# atWork_Encoder.net
KiCad netlist of a schematic drawn in Altium Designer
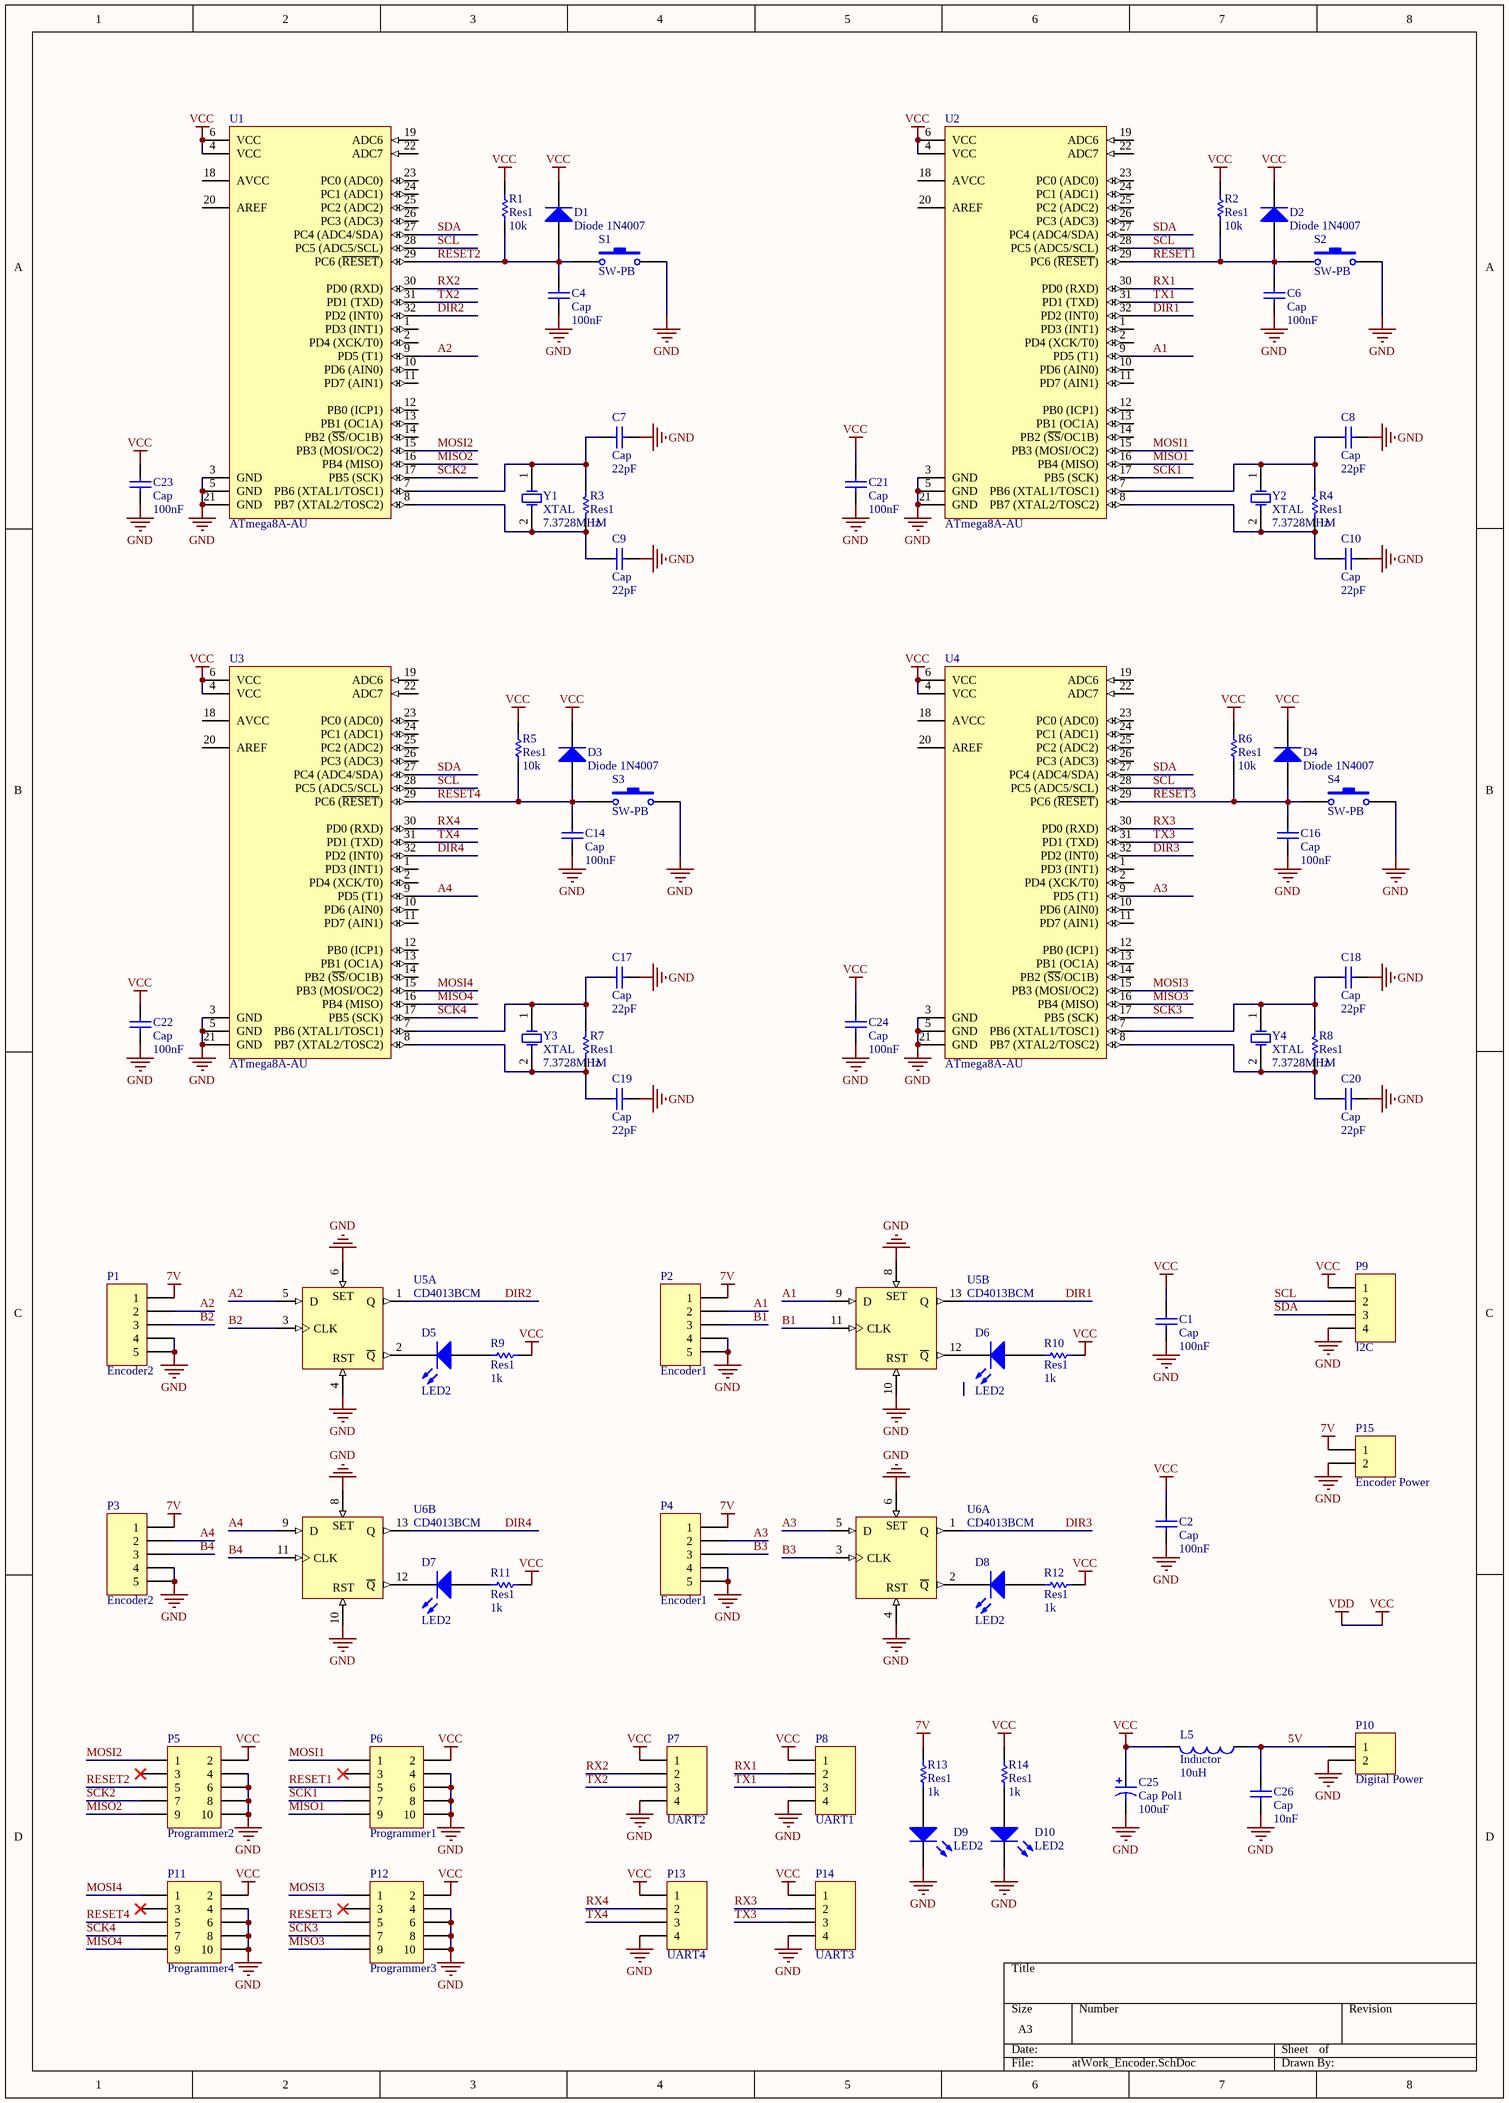
[diagram p0: atWork_Encoder.SchDoc]

(export (version "E")
  (design (tool "Eeschema 10.0.6"))
  (components
    (comp (ref "C1")
      (value "Cap")
      (footprint "C1206")
      (description "Capacitor")
      (fields (field (name "ALTIUM_VALUE") "100nF") (field (name "PUBLISHER") "Altium Limited"))
      (libsource (lib "Miscellaneous Devices") (part "Cap"))
    )
    (comp (ref "C2")
      (value "Cap")
      (footprint "C1206")
      (description "Capacitor")
      (fields (field (name "ALTIUM_VALUE") "100nF") (field (name "PUBLISHER") "Altium Limited"))
      (libsource (lib "Miscellaneous Devices") (part "Cap"))
    )
    (comp (ref "C4")
      (value "Cap")
      (footprint "C1206")
      (description "Capacitor")
      (fields (field (name "ALTIUM_VALUE") "100nF") (field (name "PUBLISHER") "Altium Limited"))
      (libsource (lib "Miscellaneous Devices") (part "Cap"))
    )
    (comp (ref "C6")
      (value "Cap")
      (footprint "C1206")
      (description "Capacitor")
      (fields (field (name "ALTIUM_VALUE") "100nF") (field (name "PUBLISHER") "Altium Limited"))
      (libsource (lib "Miscellaneous Devices") (part "Cap"))
    )
    (comp (ref "C7")
      (value "Cap")
      (footprint "C1206")
      (description "Capacitor")
      (fields (field (name "ALTIUM_VALUE") "22pF") (field (name "PUBLISHER") "Altium Limited"))
      (libsource (lib "Miscellaneous Devices") (part "Cap"))
    )
    (comp (ref "C8")
      (value "Cap")
      (footprint "C1206")
      (description "Capacitor")
      (fields (field (name "ALTIUM_VALUE") "22pF") (field (name "PUBLISHER") "Altium Limited"))
      (libsource (lib "Miscellaneous Devices") (part "Cap"))
    )
    (comp (ref "C9")
      (value "Cap")
      (footprint "C1206")
      (description "Capacitor")
      (fields (field (name "ALTIUM_VALUE") "22pF") (field (name "PUBLISHER") "Altium Limited"))
      (libsource (lib "Miscellaneous Devices") (part "Cap"))
    )
    (comp (ref "C10")
      (value "Cap")
      (footprint "C1206")
      (description "Capacitor")
      (fields (field (name "ALTIUM_VALUE") "22pF") (field (name "PUBLISHER") "Altium Limited"))
      (libsource (lib "Miscellaneous Devices") (part "Cap"))
    )
    (comp (ref "C14")
      (value "Cap")
      (footprint "C1206")
      (description "Capacitor")
      (fields (field (name "ALTIUM_VALUE") "100nF") (field (name "PUBLISHER") "Altium Limited"))
      (libsource (lib "Miscellaneous Devices") (part "Cap"))
    )
    (comp (ref "C16")
      (value "Cap")
      (footprint "C1206")
      (description "Capacitor")
      (fields (field (name "ALTIUM_VALUE") "100nF") (field (name "PUBLISHER") "Altium Limited"))
      (libsource (lib "Miscellaneous Devices") (part "Cap"))
    )
    (comp (ref "C17")
      (value "Cap")
      (footprint "C1206")
      (description "Capacitor")
      (fields (field (name "ALTIUM_VALUE") "22pF") (field (name "PUBLISHER") "Altium Limited"))
      (libsource (lib "Miscellaneous Devices") (part "Cap"))
    )
    (comp (ref "C18")
      (value "Cap")
      (footprint "C1206")
      (description "Capacitor")
      (fields (field (name "ALTIUM_VALUE") "22pF") (field (name "PUBLISHER") "Altium Limited"))
      (libsource (lib "Miscellaneous Devices") (part "Cap"))
    )
    (comp (ref "C19")
      (value "Cap")
      (footprint "C1206")
      (description "Capacitor")
      (fields (field (name "ALTIUM_VALUE") "22pF") (field (name "PUBLISHER") "Altium Limited"))
      (libsource (lib "Miscellaneous Devices") (part "Cap"))
    )
    (comp (ref "C20")
      (value "Cap")
      (footprint "C1206")
      (description "Capacitor")
      (fields (field (name "ALTIUM_VALUE") "22pF") (field (name "PUBLISHER") "Altium Limited"))
      (libsource (lib "Miscellaneous Devices") (part "Cap"))
    )
    (comp (ref "C21")
      (value "Cap")
      (footprint "C1206")
      (description "Capacitor")
      (fields (field (name "ALTIUM_VALUE") "100nF") (field (name "PUBLISHER") "Altium Limited"))
      (libsource (lib "Miscellaneous Devices") (part "Cap"))
    )
    (comp (ref "C22")
      (value "Cap")
      (footprint "C1206")
      (description "Capacitor")
      (fields (field (name "ALTIUM_VALUE") "100nF") (field (name "PUBLISHER") "Altium Limited"))
      (libsource (lib "Miscellaneous Devices") (part "Cap"))
    )
    (comp (ref "C23")
      (value "Cap")
      (footprint "C1206")
      (description "Capacitor")
      (fields (field (name "ALTIUM_VALUE") "100nF") (field (name "PUBLISHER") "Altium Limited"))
      (libsource (lib "Miscellaneous Devices") (part "Cap"))
    )
    (comp (ref "C24")
      (value "Cap")
      (footprint "C1206")
      (description "Capacitor")
      (fields (field (name "ALTIUM_VALUE") "100nF") (field (name "PUBLISHER") "Altium Limited"))
      (libsource (lib "Miscellaneous Devices") (part "Cap"))
    )
    (comp (ref "C25")
      (value "Cap Pol1")
      (footprint "CAP-SMD1")
      (description "Polarized Capacitor (Radial)")
      (fields (field (name "ALTIUM_VALUE") "100uF") (field (name "PUBLISHER") "Altium Limited"))
      (libsource (lib "Miscellaneous Devices") (part "Cap Pol1"))
    )
    (comp (ref "C26")
      (value "Cap")
      (footprint "C1206")
      (description "Capacitor")
      (fields (field (name "ALTIUM_VALUE") "10nF") (field (name "PUBLISHER") "Altium Limited"))
      (libsource (lib "Miscellaneous Devices") (part "Cap"))
    )
    (comp (ref "D1")
      (value "Diode 1N4007")
      (footprint "DIODE-SMD")
      (description "1 Amp General Purpose Rectifier")
      (fields (field (name "PUBLISHER") "Altium Limited"))
      (libsource (lib "Miscellaneous Devices") (part "Diode 1N4007"))
    )
    (comp (ref "D2")
      (value "Diode 1N4007")
      (footprint "DIODE-SMD")
      (description "1 Amp General Purpose Rectifier")
      (fields (field (name "PUBLISHER") "Altium Limited"))
      (libsource (lib "Miscellaneous Devices") (part "Diode 1N4007"))
    )
    (comp (ref "D3")
      (value "Diode 1N4007")
      (footprint "DIODE-SMD")
      (description "1 Amp General Purpose Rectifier")
      (fields (field (name "PUBLISHER") "Altium Limited"))
      (libsource (lib "Miscellaneous Devices") (part "Diode 1N4007"))
    )
    (comp (ref "D4")
      (value "Diode 1N4007")
      (footprint "DIODE-SMD")
      (description "1 Amp General Purpose Rectifier")
      (fields (field (name "PUBLISHER") "Altium Limited"))
      (libsource (lib "Miscellaneous Devices") (part "Diode 1N4007"))
    )
    (comp (ref "D5")
      (value "LED2")
      (footprint "3.2X1.6X1.1")
      (description "Typical RED, GREEN, YELLOW, AMBER GaAs LED")
      (fields (field (name "PUBLISHER") "Altium Limited"))
      (libsource (lib "Miscellaneous Devices") (part "LED2"))
    )
    (comp (ref "D6")
      (value "LED2")
      (footprint "3.2X1.6X1.1")
      (description "Typical RED, GREEN, YELLOW, AMBER GaAs LED")
      (fields (field (name "PUBLISHER") "Altium Limited"))
      (libsource (lib "Miscellaneous Devices") (part "LED2"))
    )
    (comp (ref "D7")
      (value "LED2")
      (footprint "3.2X1.6X1.1")
      (description "Typical RED, GREEN, YELLOW, AMBER GaAs LED")
      (fields (field (name "PUBLISHER") "Altium Limited"))
      (libsource (lib "Miscellaneous Devices") (part "LED2"))
    )
    (comp (ref "D8")
      (value "LED2")
      (footprint "3.2X1.6X1.1")
      (description "Typical RED, GREEN, YELLOW, AMBER GaAs LED")
      (fields (field (name "PUBLISHER") "Altium Limited"))
      (libsource (lib "Miscellaneous Devices") (part "LED2"))
    )
    (comp (ref "D9")
      (value "LED2")
      (footprint "3.2X1.6X1.1")
      (description "Typical RED, GREEN, YELLOW, AMBER GaAs LED")
      (fields (field (name "PUBLISHER") "Altium Limited"))
      (libsource (lib "Miscellaneous Devices") (part "LED2"))
    )
    (comp (ref "D10")
      (value "LED2")
      (footprint "3.2X1.6X1.1")
      (description "Typical RED, GREEN, YELLOW, AMBER GaAs LED")
      (fields (field (name "PUBLISHER") "Altium Limited"))
      (libsource (lib "Miscellaneous Devices") (part "LED2"))
    )
    (comp (ref "L5")
      (value "Inductor")
      (footprint "C1206")
      (fields (field (name "ALTIUM_VALUE") "10uH") (field (name "PUBLISHER") "Altium Limited"))
      (libsource (lib "Miscellaneous Devices") (part "Inductor"))
    )
    (comp (ref "P1")
      (value "Encoder2")
      (footprint "XH5PIN")
      (description "Header, 5-Pin")
      (fields (field (name "PUBLISHER") "Altium Limited"))
      (libsource (lib "Miscellaneous Connectors") (part "Header 5"))
    )
    (comp (ref "P2")
      (value "Encoder1")
      (footprint "XH5PIN")
      (description "Header, 5-Pin")
      (fields (field (name "PUBLISHER") "Altium Limited"))
      (libsource (lib "Miscellaneous Connectors") (part "Header 5"))
    )
    (comp (ref "P3")
      (value "Encoder2")
      (footprint "XH5PIN")
      (description "Header, 5-Pin")
      (fields (field (name "PUBLISHER") "Altium Limited"))
      (libsource (lib "Miscellaneous Connectors") (part "Header 5"))
    )
    (comp (ref "P4")
      (value "Encoder1")
      (footprint "XH5PIN")
      (description "Header, 5-Pin")
      (fields (field (name "PUBLISHER") "Altium Limited"))
      (libsource (lib "Miscellaneous Connectors") (part "Header 5"))
    )
    (comp (ref "P5")
      (value "Programmer2")
      (footprint "BOX2X5")
      (description "Box, 5-Pin, Dual row")
      (fields (field (name "DESIGNER") "Meysam Parvizi") (field (name "EMAIL") "meysam.parvizi.ir@gmail.com"))
      (libsource (lib "mp") (part "Box 5X2"))
    )
    (comp (ref "P6")
      (value "Programmer1")
      (footprint "BOX2X5")
      (description "Box, 5-Pin, Dual row")
      (fields (field (name "DESIGNER") "Meysam Parvizi") (field (name "EMAIL") "meysam.parvizi.ir@gmail.com"))
      (libsource (lib "mp") (part "Box 5X2"))
    )
    (comp (ref "P7")
      (value "UART2")
      (footprint "XH4PIN")
      (description "Header, 4-Pin")
      (fields (field (name "PUBLISHER") "Altium Limited"))
      (libsource (lib "Miscellaneous Connectors") (part "Header 4"))
    )
    (comp (ref "P8")
      (value "UART1")
      (footprint "XH4PIN")
      (description "Header, 4-Pin")
      (fields (field (name "PUBLISHER") "Altium Limited"))
      (libsource (lib "Miscellaneous Connectors") (part "Header 4"))
    )
    (comp (ref "P9")
      (value "I2C")
      (footprint "XH4PIN")
      (description "Header, 4-Pin")
      (fields (field (name "PUBLISHER") "Altium Limited"))
      (libsource (lib "Miscellaneous Connectors") (part "Header 4"))
    )
    (comp (ref "P10")
      (value "Digital Power")
      (footprint "XH2PIN")
      (description "Header, 2-Pin")
      (fields (field (name "PUBLISHER") "Altium Limited"))
      (libsource (lib "Miscellaneous Connectors") (part "Header 2"))
    )
    (comp (ref "P11")
      (value "Programmer4")
      (footprint "BOX2X5")
      (description "Box, 5-Pin, Dual row")
      (fields (field (name "DESIGNER") "Meysam Parvizi") (field (name "EMAIL") "meysam.parvizi.ir@gmail.com"))
      (libsource (lib "mp") (part "Box 5X2"))
    )
    (comp (ref "P12")
      (value "Programmer3")
      (footprint "BOX2X5")
      (description "Box, 5-Pin, Dual row")
      (fields (field (name "DESIGNER") "Meysam Parvizi") (field (name "EMAIL") "meysam.parvizi.ir@gmail.com"))
      (libsource (lib "mp") (part "Box 5X2"))
    )
    (comp (ref "P13")
      (value "UART4")
      (footprint "XH4PIN")
      (description "Header, 4-Pin")
      (fields (field (name "PUBLISHER") "Altium Limited"))
      (libsource (lib "Miscellaneous Connectors") (part "Header 4"))
    )
    (comp (ref "P14")
      (value "UART3")
      (footprint "XH4PIN")
      (description "Header, 4-Pin")
      (fields (field (name "PUBLISHER") "Altium Limited"))
      (libsource (lib "Miscellaneous Connectors") (part "Header 4"))
    )
    (comp (ref "P15")
      (value "Encoder Power")
      (footprint "XH2PIN")
      (description "Header, 2-Pin")
      (fields (field (name "PUBLISHER") "Altium Limited"))
      (libsource (lib "Miscellaneous Connectors") (part "Header 2"))
    )
    (comp (ref "R1")
      (value "Res1")
      (footprint "C1206")
      (description "Resistor")
      (fields (field (name "ALTIUM_VALUE") "10k") (field (name "PUBLISHER") "Altium Limited"))
      (libsource (lib "Miscellaneous Devices") (part "Res1"))
    )
    (comp (ref "R2")
      (value "Res1")
      (footprint "C1206")
      (description "Resistor")
      (fields (field (name "ALTIUM_VALUE") "10k") (field (name "PUBLISHER") "Altium Limited"))
      (libsource (lib "Miscellaneous Devices") (part "Res1"))
    )
    (comp (ref "R3")
      (value "Res1")
      (footprint "C1206")
      (description "Resistor")
      (fields (field (name "ALTIUM_VALUE") "1M") (field (name "PUBLISHER") "Altium Limited"))
      (libsource (lib "Miscellaneous Devices") (part "Res1"))
    )
    (comp (ref "R4")
      (value "Res1")
      (footprint "C1206")
      (description "Resistor")
      (fields (field (name "ALTIUM_VALUE") "1M") (field (name "PUBLISHER") "Altium Limited"))
      (libsource (lib "Miscellaneous Devices") (part "Res1"))
    )
    (comp (ref "R5")
      (value "Res1")
      (footprint "C1206")
      (description "Resistor")
      (fields (field (name "ALTIUM_VALUE") "10k") (field (name "PUBLISHER") "Altium Limited"))
      (libsource (lib "Miscellaneous Devices") (part "Res1"))
    )
    (comp (ref "R6")
      (value "Res1")
      (footprint "C1206")
      (description "Resistor")
      (fields (field (name "ALTIUM_VALUE") "10k") (field (name "PUBLISHER") "Altium Limited"))
      (libsource (lib "Miscellaneous Devices") (part "Res1"))
    )
    (comp (ref "R7")
      (value "Res1")
      (footprint "C1206")
      (description "Resistor")
      (fields (field (name "ALTIUM_VALUE") "1M") (field (name "PUBLISHER") "Altium Limited"))
      (libsource (lib "Miscellaneous Devices") (part "Res1"))
    )
    (comp (ref "R8")
      (value "Res1")
      (footprint "C1206")
      (description "Resistor")
      (fields (field (name "ALTIUM_VALUE") "1M") (field (name "PUBLISHER") "Altium Limited"))
      (libsource (lib "Miscellaneous Devices") (part "Res1"))
    )
    (comp (ref "R9")
      (value "Res1")
      (footprint "C1206")
      (description "Resistor")
      (fields (field (name "ALTIUM_VALUE") "1k") (field (name "PUBLISHER") "Altium Limited"))
      (libsource (lib "Miscellaneous Devices") (part "Res1"))
    )
    (comp (ref "R10")
      (value "Res1")
      (footprint "C1206")
      (description "Resistor")
      (fields (field (name "ALTIUM_VALUE") "1k") (field (name "PUBLISHER") "Altium Limited"))
      (libsource (lib "Miscellaneous Devices") (part "Res1"))
    )
    (comp (ref "R11")
      (value "Res1")
      (footprint "C1206")
      (description "Resistor")
      (fields (field (name "ALTIUM_VALUE") "1k") (field (name "PUBLISHER") "Altium Limited"))
      (libsource (lib "Miscellaneous Devices") (part "Res1"))
    )
    (comp (ref "R12")
      (value "Res1")
      (footprint "C1206")
      (description "Resistor")
      (fields (field (name "ALTIUM_VALUE") "1k") (field (name "PUBLISHER") "Altium Limited"))
      (libsource (lib "Miscellaneous Devices") (part "Res1"))
    )
    (comp (ref "R13")
      (value "Res1")
      (footprint "C1206")
      (description "Resistor")
      (fields (field (name "ALTIUM_VALUE") "1k") (field (name "PUBLISHER") "Altium Limited"))
      (libsource (lib "Miscellaneous Devices") (part "Res1"))
    )
    (comp (ref "R14")
      (value "Res1")
      (footprint "C1206")
      (description "Resistor")
      (fields (field (name "ALTIUM_VALUE") "1k") (field (name "PUBLISHER") "Altium Limited"))
      (libsource (lib "Miscellaneous Devices") (part "Res1"))
    )
    (comp (ref "S1")
      (value "SW-PB")
      (footprint "PUSH1")
      (description "Switch")
      (fields (field (name "PUBLISHER") "Altium Limited"))
      (libsource (lib "Miscellaneous Devices") (part "SW-PB"))
    )
    (comp (ref "S2")
      (value "SW-PB")
      (footprint "PUSH1")
      (description "Switch")
      (fields (field (name "PUBLISHER") "Altium Limited"))
      (libsource (lib "Miscellaneous Devices") (part "SW-PB"))
    )
    (comp (ref "S3")
      (value "SW-PB")
      (footprint "PUSH1")
      (description "Switch")
      (fields (field (name "PUBLISHER") "Altium Limited"))
      (libsource (lib "Miscellaneous Devices") (part "SW-PB"))
    )
    (comp (ref "S4")
      (value "SW-PB")
      (footprint "PUSH1")
      (description "Switch")
      (fields (field (name "PUBLISHER") "Altium Limited"))
      (libsource (lib "Miscellaneous Devices") (part "SW-PB"))
    )
    (comp (ref "U1")
      (value "ATmega8A-AU")
      (footprint "32A_M")
      (fields (field (name "PUBLISHER") "Altium Limited"))
      (libsource (lib "Atmel Microcontroller 8-Bit megaAVR") (part "ATmega8A-AU"))
    )
    (comp (ref "U2")
      (value "ATmega8A-AU")
      (footprint "32A_M")
      (fields (field (name "PUBLISHER") "Altium Limited"))
      (libsource (lib "Atmel Microcontroller 8-Bit megaAVR") (part "ATmega8A-AU"))
    )
    (comp (ref "U3")
      (value "ATmega8A-AU")
      (footprint "32A_M")
      (fields (field (name "PUBLISHER") "Altium Limited"))
      (libsource (lib "Atmel Microcontroller 8-Bit megaAVR") (part "ATmega8A-AU"))
    )
    (comp (ref "U4")
      (value "ATmega8A-AU")
      (footprint "32A_M")
      (fields (field (name "PUBLISHER") "Altium Limited"))
      (libsource (lib "Atmel Microcontroller 8-Bit megaAVR") (part "ATmega8A-AU"))
    )
    (comp (ref "U5")
      (value "CD4013BCM")
      (footprint "M14A_M")
      (description "Dual D-Type Flip-Flop")
      (fields (field (name "PUBLISHER") "Altium Limited"))
      (libsource (lib "FSC Logic Flip-Flop") (part "CD4013BCM"))
    )
    (comp (ref "U6")
      (value "CD4013BCM")
      (footprint "M14A_M")
      (description "Dual D-Type Flip-Flop")
      (fields (field (name "PUBLISHER") "Altium Limited"))
      (libsource (lib "FSC Logic Flip-Flop") (part "CD4013BCM"))
    )
    (comp (ref "Y1")
      (value "XTAL")
      (footprint "XTAL")
      (description "Crystal Oscillator")
      (fields
        (field (name "ALTIUM_VALUE") "7.3728MHz")
        (field (name "DESIGNER") "Meysam Parvizi")
        (field (name "EMAIL") "meysam.parvizi.ir@gmail.com")
      )
      (libsource (lib "mp") (part "XTAL"))
    )
    (comp (ref "Y2")
      (value "XTAL")
      (footprint "XTAL")
      (description "Crystal Oscillator")
      (fields
        (field (name "ALTIUM_VALUE") "7.3728MHz")
        (field (name "DESIGNER") "Meysam Parvizi")
        (field (name "EMAIL") "meysam.parvizi.ir@gmail.com")
      )
      (libsource (lib "mp") (part "XTAL"))
    )
    (comp (ref "Y3")
      (value "XTAL")
      (footprint "XTAL")
      (description "Crystal Oscillator")
      (fields
        (field (name "ALTIUM_VALUE") "7.3728MHz")
        (field (name "DESIGNER") "Meysam Parvizi")
        (field (name "EMAIL") "meysam.parvizi.ir@gmail.com")
      )
      (libsource (lib "mp") (part "XTAL"))
    )
    (comp (ref "Y4")
      (value "XTAL")
      (footprint "XTAL")
      (description "Crystal Oscillator")
      (fields
        (field (name "ALTIUM_VALUE") "7.3728MHz")
        (field (name "DESIGNER") "Meysam Parvizi")
        (field (name "EMAIL") "meysam.parvizi.ir@gmail.com")
      )
      (libsource (lib "mp") (part "XTAL"))
    )
  )
  (nets
    (net (code "1") (name "/5V") (class "Default")
      (node (ref "C26") (pin "2") (pinfunction "2_2") (pintype "passive"))
      (node (ref "L5") (pin "1") (pinfunction "1_1") (pintype "passive"))
      (node (ref "P10") (pin "1") (pinfunction "1_1") (pintype "passive"))
    )
    (net (code "2") (name "/A1") (class "Default")
      (node (ref "P2") (pin "2") (pinfunction "2_2") (pintype "passive"))
      (node (ref "U2") (pin "9") (pinfunction "PD5_(T1)_9") (pintype "bidirectional"))
      (node (ref "U5") (pin "9") (pinfunction "D_9") (pintype "input"))
    )
    (net (code "3") (name "/A2") (class "Default")
      (node (ref "P1") (pin "2") (pinfunction "2_2") (pintype "passive"))
      (node (ref "U1") (pin "9") (pinfunction "PD5_(T1)_9") (pintype "bidirectional"))
      (node (ref "U5") (pin "5") (pinfunction "D_5") (pintype "input"))
    )
    (net (code "4") (name "/A3") (class "Default")
      (node (ref "P4") (pin "2") (pinfunction "2_2") (pintype "passive"))
      (node (ref "U4") (pin "9") (pinfunction "PD5_(T1)_9") (pintype "bidirectional"))
      (node (ref "U6") (pin "5") (pinfunction "D_5") (pintype "input"))
    )
    (net (code "5") (name "/A4") (class "Default")
      (node (ref "P3") (pin "2") (pinfunction "2_2") (pintype "passive"))
      (node (ref "U3") (pin "9") (pinfunction "PD5_(T1)_9") (pintype "bidirectional"))
      (node (ref "U6") (pin "9") (pinfunction "D_9") (pintype "input"))
    )
    (net (code "6") (name "/B1") (class "Default")
      (node (ref "P2") (pin "3") (pinfunction "3_3") (pintype "passive"))
      (node (ref "U5") (pin "11") (pinfunction "CLK_11") (pintype "input"))
    )
    (net (code "7") (name "/B2") (class "Default")
      (node (ref "P1") (pin "3") (pinfunction "3_3") (pintype "passive"))
      (node (ref "U5") (pin "3") (pinfunction "CLK_3") (pintype "input"))
    )
    (net (code "8") (name "/B3") (class "Default")
      (node (ref "P4") (pin "3") (pinfunction "3_3") (pintype "passive"))
      (node (ref "U6") (pin "3") (pinfunction "CLK_3") (pintype "input"))
    )
    (net (code "9") (name "/B4") (class "Default")
      (node (ref "P3") (pin "3") (pinfunction "3_3") (pintype "passive"))
      (node (ref "U6") (pin "11") (pinfunction "CLK_11") (pintype "input"))
    )
    (net (code "10") (name "/DIR1") (class "Default")
      (node (ref "U2") (pin "32") (pinfunction "PD2_(INT0)_32") (pintype "bidirectional"))
      (node (ref "U5") (pin "13") (pinfunction "Q_13") (pintype "output"))
    )
    (net (code "11") (name "/DIR2") (class "Default")
      (node (ref "U1") (pin "32") (pinfunction "PD2_(INT0)_32") (pintype "bidirectional"))
      (node (ref "U5") (pin "1") (pinfunction "Q_1") (pintype "output"))
    )
    (net (code "12") (name "/DIR3") (class "Default")
      (node (ref "U4") (pin "32") (pinfunction "PD2_(INT0)_32") (pintype "bidirectional"))
      (node (ref "U6") (pin "1") (pinfunction "Q_1") (pintype "output"))
    )
    (net (code "13") (name "/DIR4") (class "Default")
      (node (ref "U3") (pin "32") (pinfunction "PD2_(INT0)_32") (pintype "bidirectional"))
      (node (ref "U6") (pin "13") (pinfunction "Q_13") (pintype "output"))
    )
    (net (code "14") (name "/MISO1") (class "Default")
      (node (ref "P6") (pin "9") (pinfunction "9_9") (pintype "passive"))
      (node (ref "U2") (pin "16") (pinfunction "PB4_(MISO)_16") (pintype "bidirectional"))
    )
    (net (code "15") (name "/MISO2") (class "Default")
      (node (ref "P5") (pin "9") (pinfunction "9_9") (pintype "passive"))
      (node (ref "U1") (pin "16") (pinfunction "PB4_(MISO)_16") (pintype "bidirectional"))
    )
    (net (code "16") (name "/MISO3") (class "Default")
      (node (ref "P12") (pin "9") (pinfunction "9_9") (pintype "passive"))
      (node (ref "U4") (pin "16") (pinfunction "PB4_(MISO)_16") (pintype "bidirectional"))
    )
    (net (code "17") (name "/MISO4") (class "Default")
      (node (ref "P11") (pin "9") (pinfunction "9_9") (pintype "passive"))
      (node (ref "U3") (pin "16") (pinfunction "PB4_(MISO)_16") (pintype "bidirectional"))
    )
    (net (code "18") (name "/MOSI1") (class "Default")
      (node (ref "P6") (pin "1") (pinfunction "1_1") (pintype "passive"))
      (node (ref "U2") (pin "15") (pinfunction "PB3_(MOSI/OC2)_15") (pintype "bidirectional"))
    )
    (net (code "19") (name "/MOSI2") (class "Default")
      (node (ref "P5") (pin "1") (pinfunction "1_1") (pintype "passive"))
      (node (ref "U1") (pin "15") (pinfunction "PB3_(MOSI/OC2)_15") (pintype "bidirectional"))
    )
    (net (code "20") (name "/MOSI3") (class "Default")
      (node (ref "P12") (pin "1") (pinfunction "1_1") (pintype "passive"))
      (node (ref "U4") (pin "15") (pinfunction "PB3_(MOSI/OC2)_15") (pintype "bidirectional"))
    )
    (net (code "21") (name "/MOSI4") (class "Default")
      (node (ref "P11") (pin "1") (pinfunction "1_1") (pintype "passive"))
      (node (ref "U3") (pin "15") (pinfunction "PB3_(MOSI/OC2)_15") (pintype "bidirectional"))
    )
    (net (code "22") (name "/RESET1") (class "Default")
      (node (ref "C6") (pin "2") (pinfunction "2_2") (pintype "passive"))
      (node (ref "D2") (pin "1") (pinfunction "A_1") (pintype "passive"))
      (node (ref "P6") (pin "5") (pinfunction "5_5") (pintype "passive"))
      (node (ref "R2") (pin "2") (pinfunction "2_2") (pintype "passive"))
      (node (ref "S2") (pin "1") (pinfunction "1_1") (pintype "passive"))
      (node (ref "U2") (pin "29") (pinfunction "PC6_(~{RESET})_29") (pintype "bidirectional"))
    )
    (net (code "23") (name "/RESET2") (class "Default")
      (node (ref "C4") (pin "2") (pinfunction "2_2") (pintype "passive"))
      (node (ref "D1") (pin "1") (pinfunction "A_1") (pintype "passive"))
      (node (ref "P5") (pin "5") (pinfunction "5_5") (pintype "passive"))
      (node (ref "R1") (pin "2") (pinfunction "2_2") (pintype "passive"))
      (node (ref "S1") (pin "1") (pinfunction "1_1") (pintype "passive"))
      (node (ref "U1") (pin "29") (pinfunction "PC6_(~{RESET})_29") (pintype "bidirectional"))
    )
    (net (code "24") (name "/RESET3") (class "Default")
      (node (ref "C16") (pin "2") (pinfunction "2_2") (pintype "passive"))
      (node (ref "D4") (pin "1") (pinfunction "A_1") (pintype "passive"))
      (node (ref "P12") (pin "5") (pinfunction "5_5") (pintype "passive"))
      (node (ref "R6") (pin "2") (pinfunction "2_2") (pintype "passive"))
      (node (ref "S4") (pin "1") (pinfunction "1_1") (pintype "passive"))
      (node (ref "U4") (pin "29") (pinfunction "PC6_(~{RESET})_29") (pintype "bidirectional"))
    )
    (net (code "25") (name "/RESET4") (class "Default")
      (node (ref "C14") (pin "2") (pinfunction "2_2") (pintype "passive"))
      (node (ref "D3") (pin "1") (pinfunction "A_1") (pintype "passive"))
      (node (ref "P11") (pin "5") (pinfunction "5_5") (pintype "passive"))
      (node (ref "R5") (pin "2") (pinfunction "2_2") (pintype "passive"))
      (node (ref "S3") (pin "1") (pinfunction "1_1") (pintype "passive"))
      (node (ref "U3") (pin "29") (pinfunction "PC6_(~{RESET})_29") (pintype "bidirectional"))
    )
    (net (code "26") (name "/RX1") (class "Default")
      (node (ref "P8") (pin "2") (pinfunction "2_2") (pintype "passive"))
      (node (ref "U2") (pin "30") (pinfunction "PD0_(RXD)_30") (pintype "bidirectional"))
    )
    (net (code "27") (name "/RX2") (class "Default")
      (node (ref "P7") (pin "2") (pinfunction "2_2") (pintype "passive"))
      (node (ref "U1") (pin "30") (pinfunction "PD0_(RXD)_30") (pintype "bidirectional"))
    )
    (net (code "28") (name "/RX3") (class "Default")
      (node (ref "P14") (pin "2") (pinfunction "2_2") (pintype "passive"))
      (node (ref "U4") (pin "30") (pinfunction "PD0_(RXD)_30") (pintype "bidirectional"))
    )
    (net (code "29") (name "/RX4") (class "Default")
      (node (ref "P13") (pin "2") (pinfunction "2_2") (pintype "passive"))
      (node (ref "U3") (pin "30") (pinfunction "PD0_(RXD)_30") (pintype "bidirectional"))
    )
    (net (code "30") (name "/SCK1") (class "Default")
      (node (ref "P6") (pin "7") (pinfunction "7_7") (pintype "passive"))
      (node (ref "U2") (pin "17") (pinfunction "PB5_(SCK)_17") (pintype "bidirectional"))
    )
    (net (code "31") (name "/SCK2") (class "Default")
      (node (ref "P5") (pin "7") (pinfunction "7_7") (pintype "passive"))
      (node (ref "U1") (pin "17") (pinfunction "PB5_(SCK)_17") (pintype "bidirectional"))
    )
    (net (code "32") (name "/SCK3") (class "Default")
      (node (ref "P12") (pin "7") (pinfunction "7_7") (pintype "passive"))
      (node (ref "U4") (pin "17") (pinfunction "PB5_(SCK)_17") (pintype "bidirectional"))
    )
    (net (code "33") (name "/SCK4") (class "Default")
      (node (ref "P11") (pin "7") (pinfunction "7_7") (pintype "passive"))
      (node (ref "U3") (pin "17") (pinfunction "PB5_(SCK)_17") (pintype "bidirectional"))
    )
    (net (code "34") (name "/SCL") (class "Default")
      (node (ref "P9") (pin "2") (pinfunction "2_2") (pintype "passive"))
      (node (ref "U1") (pin "28") (pinfunction "PC5_(ADC5/SCL)_28") (pintype "bidirectional"))
      (node (ref "U2") (pin "28") (pinfunction "PC5_(ADC5/SCL)_28") (pintype "bidirectional"))
      (node (ref "U3") (pin "28") (pinfunction "PC5_(ADC5/SCL)_28") (pintype "bidirectional"))
      (node (ref "U4") (pin "28") (pinfunction "PC5_(ADC5/SCL)_28") (pintype "bidirectional"))
    )
    (net (code "35") (name "/SDA") (class "Default")
      (node (ref "P9") (pin "3") (pinfunction "3_3") (pintype "passive"))
      (node (ref "U1") (pin "27") (pinfunction "PC4_(ADC4/SDA)_27") (pintype "bidirectional"))
      (node (ref "U2") (pin "27") (pinfunction "PC4_(ADC4/SDA)_27") (pintype "bidirectional"))
      (node (ref "U3") (pin "27") (pinfunction "PC4_(ADC4/SDA)_27") (pintype "bidirectional"))
      (node (ref "U4") (pin "27") (pinfunction "PC4_(ADC4/SDA)_27") (pintype "bidirectional"))
    )
    (net (code "36") (name "/TX1") (class "Default")
      (node (ref "P8") (pin "3") (pinfunction "3_3") (pintype "passive"))
      (node (ref "U2") (pin "31") (pinfunction "PD1_(TXD)_31") (pintype "bidirectional"))
    )
    (net (code "37") (name "/TX2") (class "Default")
      (node (ref "P7") (pin "3") (pinfunction "3_3") (pintype "passive"))
      (node (ref "U1") (pin "31") (pinfunction "PD1_(TXD)_31") (pintype "bidirectional"))
    )
    (net (code "38") (name "/TX3") (class "Default")
      (node (ref "P14") (pin "3") (pinfunction "3_3") (pintype "passive"))
      (node (ref "U4") (pin "31") (pinfunction "PD1_(TXD)_31") (pintype "bidirectional"))
    )
    (net (code "39") (name "/TX4") (class "Default")
      (node (ref "P13") (pin "3") (pinfunction "3_3") (pintype "passive"))
      (node (ref "U3") (pin "31") (pinfunction "PD1_(TXD)_31") (pintype "bidirectional"))
    )
    (net (code "40") (name "7V") (class "Default")
      (node (ref "P1") (pin "1") (pinfunction "1_1") (pintype "passive"))
      (node (ref "P15") (pin "1") (pinfunction "1_1") (pintype "passive"))
      (node (ref "P2") (pin "1") (pinfunction "1_1") (pintype "passive"))
      (node (ref "P3") (pin "1") (pinfunction "1_1") (pintype "passive"))
      (node (ref "P4") (pin "1") (pinfunction "1_1") (pintype "passive"))
      (node (ref "R13") (pin "2") (pinfunction "2_2") (pintype "passive"))
    )
    (net (code "41") (name "GND") (class "Default")
      (node (ref "C1") (pin "1") (pinfunction "1_1") (pintype "passive"))
      (node (ref "C10") (pin "1") (pinfunction "1_1") (pintype "passive"))
      (node (ref "C14") (pin "1") (pinfunction "1_1") (pintype "passive"))
      (node (ref "C16") (pin "1") (pinfunction "1_1") (pintype "passive"))
      (node (ref "C17") (pin "1") (pinfunction "1_1") (pintype "passive"))
      (node (ref "C18") (pin "1") (pinfunction "1_1") (pintype "passive"))
      (node (ref "C19") (pin "1") (pinfunction "1_1") (pintype "passive"))
      (node (ref "C2") (pin "1") (pinfunction "1_1") (pintype "passive"))
      (node (ref "C20") (pin "1") (pinfunction "1_1") (pintype "passive"))
      (node (ref "C21") (pin "1") (pinfunction "1_1") (pintype "passive"))
      (node (ref "C22") (pin "1") (pinfunction "1_1") (pintype "passive"))
      (node (ref "C23") (pin "1") (pinfunction "1_1") (pintype "passive"))
      (node (ref "C24") (pin "1") (pinfunction "1_1") (pintype "passive"))
      (node (ref "C25") (pin "2") (pinfunction "2_2") (pintype "passive"))
      (node (ref "C26") (pin "1") (pinfunction "1_1") (pintype "passive"))
      (node (ref "C4") (pin "1") (pinfunction "1_1") (pintype "passive"))
      (node (ref "C6") (pin "1") (pinfunction "1_1") (pintype "passive"))
      (node (ref "C7") (pin "1") (pinfunction "1_1") (pintype "passive"))
      (node (ref "C8") (pin "1") (pinfunction "1_1") (pintype "passive"))
      (node (ref "C9") (pin "1") (pinfunction "1_1") (pintype "passive"))
      (node (ref "D10") (pin "2") (pinfunction "K_2") (pintype "passive"))
      (node (ref "D9") (pin "2") (pinfunction "K_2") (pintype "passive"))
      (node (ref "P1") (pin "4") (pinfunction "4_4") (pintype "passive"))
      (node (ref "P1") (pin "5") (pinfunction "5_5") (pintype "passive"))
      (node (ref "P10") (pin "2") (pinfunction "2_2") (pintype "passive"))
      (node (ref "P11") (pin "10") (pinfunction "10_10") (pintype "passive"))
      (node (ref "P11") (pin "4") (pinfunction "4_4") (pintype "passive"))
      (node (ref "P11") (pin "6") (pinfunction "6_6") (pintype "passive"))
      (node (ref "P11") (pin "8") (pinfunction "8_8") (pintype "passive"))
      (node (ref "P12") (pin "10") (pinfunction "10_10") (pintype "passive"))
      (node (ref "P12") (pin "4") (pinfunction "4_4") (pintype "passive"))
      (node (ref "P12") (pin "6") (pinfunction "6_6") (pintype "passive"))
      (node (ref "P12") (pin "8") (pinfunction "8_8") (pintype "passive"))
      (node (ref "P13") (pin "4") (pinfunction "4_4") (pintype "passive"))
      (node (ref "P14") (pin "4") (pinfunction "4_4") (pintype "passive"))
      (node (ref "P15") (pin "2") (pinfunction "2_2") (pintype "passive"))
      (node (ref "P2") (pin "4") (pinfunction "4_4") (pintype "passive"))
      (node (ref "P2") (pin "5") (pinfunction "5_5") (pintype "passive"))
      (node (ref "P3") (pin "4") (pinfunction "4_4") (pintype "passive"))
      (node (ref "P3") (pin "5") (pinfunction "5_5") (pintype "passive"))
      (node (ref "P4") (pin "4") (pinfunction "4_4") (pintype "passive"))
      (node (ref "P4") (pin "5") (pinfunction "5_5") (pintype "passive"))
      (node (ref "P5") (pin "10") (pinfunction "10_10") (pintype "passive"))
      (node (ref "P5") (pin "4") (pinfunction "4_4") (pintype "passive"))
      (node (ref "P5") (pin "6") (pinfunction "6_6") (pintype "passive"))
      (node (ref "P5") (pin "8") (pinfunction "8_8") (pintype "passive"))
      (node (ref "P6") (pin "10") (pinfunction "10_10") (pintype "passive"))
      (node (ref "P6") (pin "4") (pinfunction "4_4") (pintype "passive"))
      (node (ref "P6") (pin "6") (pinfunction "6_6") (pintype "passive"))
      (node (ref "P6") (pin "8") (pinfunction "8_8") (pintype "passive"))
      (node (ref "P7") (pin "4") (pinfunction "4_4") (pintype "passive"))
      (node (ref "P8") (pin "4") (pinfunction "4_4") (pintype "passive"))
      (node (ref "P9") (pin "4") (pinfunction "4_4") (pintype "passive"))
      (node (ref "S1") (pin "2") (pinfunction "2_2") (pintype "passive"))
      (node (ref "S2") (pin "2") (pinfunction "2_2") (pintype "passive"))
      (node (ref "S3") (pin "2") (pinfunction "2_2") (pintype "passive"))
      (node (ref "S4") (pin "2") (pinfunction "2_2") (pintype "passive"))
      (node (ref "U1") (pin "21") (pinfunction "GND_21") (pintype "power_in"))
      (node (ref "U1") (pin "3") (pinfunction "GND_3") (pintype "power_in"))
      (node (ref "U1") (pin "5") (pinfunction "GND_5") (pintype "power_in"))
      (node (ref "U2") (pin "21") (pinfunction "GND_21") (pintype "power_in"))
      (node (ref "U2") (pin "3") (pinfunction "GND_3") (pintype "power_in"))
      (node (ref "U2") (pin "5") (pinfunction "GND_5") (pintype "power_in"))
      (node (ref "U3") (pin "21") (pinfunction "GND_21") (pintype "power_in"))
      (node (ref "U3") (pin "3") (pinfunction "GND_3") (pintype "power_in"))
      (node (ref "U3") (pin "5") (pinfunction "GND_5") (pintype "power_in"))
      (node (ref "U4") (pin "21") (pinfunction "GND_21") (pintype "power_in"))
      (node (ref "U4") (pin "3") (pinfunction "GND_3") (pintype "power_in"))
      (node (ref "U4") (pin "5") (pinfunction "GND_5") (pintype "power_in"))
      (node (ref "U5") (pin "10") (pinfunction "RST_10") (pintype "input"))
      (node (ref "U5") (pin "4") (pinfunction "RST_4") (pintype "input"))
      (node (ref "U5") (pin "6") (pinfunction "S_6") (pintype "input"))
      (node (ref "U5") (pin "7") (pinfunction "GND_7") (pintype "power_in"))
      (node (ref "U5") (pin "8") (pinfunction "S_8") (pintype "input"))
      (node (ref "U6") (pin "10") (pinfunction "RST_10") (pintype "input"))
      (node (ref "U6") (pin "4") (pinfunction "RST_4") (pintype "input"))
      (node (ref "U6") (pin "6") (pinfunction "S_6") (pintype "input"))
      (node (ref "U6") (pin "7") (pinfunction "GND_7") (pintype "power_in"))
      (node (ref "U6") (pin "8") (pinfunction "S_8") (pintype "input"))
    )
    (net (code "42") (name "Net-(D5-A)") (class "Default")
      (node (ref "D5") (pin "1") (pinfunction "A_1") (pintype "passive"))
      (node (ref "R9") (pin "2") (pinfunction "2_2") (pintype "passive"))
    )
    (net (code "43") (name "Net-(D5-K)") (class "Default")
      (node (ref "D5") (pin "2") (pinfunction "K_2") (pintype "passive"))
      (node (ref "U5") (pin "2") (pinfunction "~{Q}_2") (pintype "output"))
    )
    (net (code "44") (name "Net-(D6-A)") (class "Default")
      (node (ref "D6") (pin "1") (pinfunction "A_1") (pintype "passive"))
      (node (ref "R10") (pin "2") (pinfunction "2_2") (pintype "passive"))
    )
    (net (code "45") (name "Net-(D6-K)") (class "Default")
      (node (ref "D6") (pin "2") (pinfunction "K_2") (pintype "passive"))
      (node (ref "U5") (pin "12") (pinfunction "~{Q}_12") (pintype "output"))
    )
    (net (code "46") (name "Net-(D7-A)") (class "Default")
      (node (ref "D7") (pin "1") (pinfunction "A_1") (pintype "passive"))
      (node (ref "R11") (pin "2") (pinfunction "2_2") (pintype "passive"))
    )
    (net (code "47") (name "Net-(D7-K)") (class "Default")
      (node (ref "D7") (pin "2") (pinfunction "K_2") (pintype "passive"))
      (node (ref "U6") (pin "12") (pinfunction "~{Q}_12") (pintype "output"))
    )
    (net (code "48") (name "Net-(D8-A)") (class "Default")
      (node (ref "D8") (pin "1") (pinfunction "A_1") (pintype "passive"))
      (node (ref "R12") (pin "2") (pinfunction "2_2") (pintype "passive"))
    )
    (net (code "49") (name "Net-(D8-K)") (class "Default")
      (node (ref "D8") (pin "2") (pinfunction "K_2") (pintype "passive"))
      (node (ref "U6") (pin "2") (pinfunction "~{Q}_2") (pintype "output"))
    )
    (net (code "50") (name "Net-(D9-A)") (class "Default")
      (node (ref "D9") (pin "1") (pinfunction "A_1") (pintype "passive"))
      (node (ref "R13") (pin "1") (pinfunction "1_1") (pintype "passive"))
    )
    (net (code "51") (name "Net-(D10-A)") (class "Default")
      (node (ref "D10") (pin "1") (pinfunction "A_1") (pintype "passive"))
      (node (ref "R14") (pin "1") (pinfunction "1_1") (pintype "passive"))
    )
    (net (code "52") (name "Net-(U1-PB6_(XTAL1{slash}TOSC1))") (class "Default")
      (node (ref "C7") (pin "2") (pinfunction "2_2") (pintype "passive"))
      (node (ref "R3") (pin "2") (pinfunction "2_2") (pintype "passive"))
      (node (ref "U1") (pin "7") (pinfunction "PB6_(XTAL1/TOSC1)_7") (pintype "bidirectional"))
      (node (ref "Y1") (pin "1") (pinfunction "OSC1_1") (pintype "passive"))
    )
    (net (code "53") (name "Net-(U1-PB7_(XTAL2{slash}TOSC2))") (class "Default")
      (node (ref "C9") (pin "2") (pinfunction "2_2") (pintype "passive"))
      (node (ref "R3") (pin "1") (pinfunction "1_1") (pintype "passive"))
      (node (ref "U1") (pin "8") (pinfunction "PB7_(XTAL2/TOSC2)_8") (pintype "bidirectional"))
      (node (ref "Y1") (pin "2") (pinfunction "OSC2_2") (pintype "passive"))
    )
    (net (code "54") (name "Net-(U2-PB6_(XTAL1{slash}TOSC1))") (class "Default")
      (node (ref "C8") (pin "2") (pinfunction "2_2") (pintype "passive"))
      (node (ref "R4") (pin "2") (pinfunction "2_2") (pintype "passive"))
      (node (ref "U2") (pin "7") (pinfunction "PB6_(XTAL1/TOSC1)_7") (pintype "bidirectional"))
      (node (ref "Y2") (pin "1") (pinfunction "OSC1_1") (pintype "passive"))
    )
    (net (code "55") (name "Net-(U2-PB7_(XTAL2{slash}TOSC2))") (class "Default")
      (node (ref "C10") (pin "2") (pinfunction "2_2") (pintype "passive"))
      (node (ref "R4") (pin "1") (pinfunction "1_1") (pintype "passive"))
      (node (ref "U2") (pin "8") (pinfunction "PB7_(XTAL2/TOSC2)_8") (pintype "bidirectional"))
      (node (ref "Y2") (pin "2") (pinfunction "OSC2_2") (pintype "passive"))
    )
    (net (code "56") (name "Net-(U3-PB6_(XTAL1{slash}TOSC1))") (class "Default")
      (node (ref "C17") (pin "2") (pinfunction "2_2") (pintype "passive"))
      (node (ref "R7") (pin "2") (pinfunction "2_2") (pintype "passive"))
      (node (ref "U3") (pin "7") (pinfunction "PB6_(XTAL1/TOSC1)_7") (pintype "bidirectional"))
      (node (ref "Y3") (pin "1") (pinfunction "OSC1_1") (pintype "passive"))
    )
    (net (code "57") (name "Net-(U3-PB7_(XTAL2{slash}TOSC2))") (class "Default")
      (node (ref "C19") (pin "2") (pinfunction "2_2") (pintype "passive"))
      (node (ref "R7") (pin "1") (pinfunction "1_1") (pintype "passive"))
      (node (ref "U3") (pin "8") (pinfunction "PB7_(XTAL2/TOSC2)_8") (pintype "bidirectional"))
      (node (ref "Y3") (pin "2") (pinfunction "OSC2_2") (pintype "passive"))
    )
    (net (code "58") (name "Net-(U4-PB6_(XTAL1{slash}TOSC1))") (class "Default")
      (node (ref "C18") (pin "2") (pinfunction "2_2") (pintype "passive"))
      (node (ref "R8") (pin "2") (pinfunction "2_2") (pintype "passive"))
      (node (ref "U4") (pin "7") (pinfunction "PB6_(XTAL1/TOSC1)_7") (pintype "bidirectional"))
      (node (ref "Y4") (pin "1") (pinfunction "OSC1_1") (pintype "passive"))
    )
    (net (code "59") (name "Net-(U4-PB7_(XTAL2{slash}TOSC2))") (class "Default")
      (node (ref "C20") (pin "2") (pinfunction "2_2") (pintype "passive"))
      (node (ref "R8") (pin "1") (pinfunction "1_1") (pintype "passive"))
      (node (ref "U4") (pin "8") (pinfunction "PB7_(XTAL2/TOSC2)_8") (pintype "bidirectional"))
      (node (ref "Y4") (pin "2") (pinfunction "OSC2_2") (pintype "passive"))
    )
    (net (code "60") (name "VCC") (class "Default")
      (node (ref "C1") (pin "2") (pinfunction "2_2") (pintype "passive"))
      (node (ref "C2") (pin "2") (pinfunction "2_2") (pintype "passive"))
      (node (ref "C21") (pin "2") (pinfunction "2_2") (pintype "passive"))
      (node (ref "C22") (pin "2") (pinfunction "2_2") (pintype "passive"))
      (node (ref "C23") (pin "2") (pinfunction "2_2") (pintype "passive"))
      (node (ref "C24") (pin "2") (pinfunction "2_2") (pintype "passive"))
      (node (ref "C25") (pin "1") (pinfunction "1_1") (pintype "passive"))
      (node (ref "D1") (pin "2") (pinfunction "K_2") (pintype "passive"))
      (node (ref "D2") (pin "2") (pinfunction "K_2") (pintype "passive"))
      (node (ref "D3") (pin "2") (pinfunction "K_2") (pintype "passive"))
      (node (ref "D4") (pin "2") (pinfunction "K_2") (pintype "passive"))
      (node (ref "L5") (pin "2") (pinfunction "2_2") (pintype "passive"))
      (node (ref "P11") (pin "2") (pinfunction "2_2") (pintype "passive"))
      (node (ref "P12") (pin "2") (pinfunction "2_2") (pintype "passive"))
      (node (ref "P13") (pin "1") (pinfunction "1_1") (pintype "passive"))
      (node (ref "P14") (pin "1") (pinfunction "1_1") (pintype "passive"))
      (node (ref "P5") (pin "2") (pinfunction "2_2") (pintype "passive"))
      (node (ref "P6") (pin "2") (pinfunction "2_2") (pintype "passive"))
      (node (ref "P7") (pin "1") (pinfunction "1_1") (pintype "passive"))
      (node (ref "P8") (pin "1") (pinfunction "1_1") (pintype "passive"))
      (node (ref "P9") (pin "1") (pinfunction "1_1") (pintype "passive"))
      (node (ref "R1") (pin "1") (pinfunction "1_1") (pintype "passive"))
      (node (ref "R10") (pin "1") (pinfunction "1_1") (pintype "passive"))
      (node (ref "R11") (pin "1") (pinfunction "1_1") (pintype "passive"))
      (node (ref "R12") (pin "1") (pinfunction "1_1") (pintype "passive"))
      (node (ref "R14") (pin "2") (pinfunction "2_2") (pintype "passive"))
      (node (ref "R2") (pin "1") (pinfunction "1_1") (pintype "passive"))
      (node (ref "R5") (pin "1") (pinfunction "1_1") (pintype "passive"))
      (node (ref "R6") (pin "1") (pinfunction "1_1") (pintype "passive"))
      (node (ref "R9") (pin "1") (pinfunction "1_1") (pintype "passive"))
      (node (ref "U1") (pin "4") (pinfunction "VCC_4") (pintype "power_in"))
      (node (ref "U1") (pin "6") (pinfunction "VCC_6") (pintype "power_in"))
      (node (ref "U2") (pin "4") (pinfunction "VCC_4") (pintype "power_in"))
      (node (ref "U2") (pin "6") (pinfunction "VCC_6") (pintype "power_in"))
      (node (ref "U3") (pin "4") (pinfunction "VCC_4") (pintype "power_in"))
      (node (ref "U3") (pin "6") (pinfunction "VCC_6") (pintype "power_in"))
      (node (ref "U4") (pin "4") (pinfunction "VCC_4") (pintype "power_in"))
      (node (ref "U4") (pin "6") (pinfunction "VCC_6") (pintype "power_in"))
      (node (ref "U5") (pin "14") (pinfunction "VDD_14") (pintype "power_in"))
      (node (ref "U6") (pin "14") (pinfunction "VDD_14") (pintype "power_in"))
    )
    (net (code "61") (name "unconnected-(P5-Pad3)") (class "Default")
      (node (ref "P5") (pin "3") (pinfunction "3_3") (pintype "passive+no_connect"))
    )
    (net (code "62") (name "unconnected-(P6-Pad3)") (class "Default")
      (node (ref "P6") (pin "3") (pinfunction "3_3") (pintype "passive+no_connect"))
    )
    (net (code "63") (name "unconnected-(P11-Pad3)") (class "Default")
      (node (ref "P11") (pin "3") (pinfunction "3_3") (pintype "passive+no_connect"))
    )
    (net (code "64") (name "unconnected-(P12-Pad3)") (class "Default")
      (node (ref "P12") (pin "3") (pinfunction "3_3") (pintype "passive+no_connect"))
    )
    (net (code "65") (name "unconnected-(U1-ADC6-Pad19)") (class "Default")
      (node (ref "U1") (pin "19") (pinfunction "ADC6_19") (pintype "input"))
    )
    (net (code "66") (name "unconnected-(U1-ADC7-Pad22)") (class "Default")
      (node (ref "U1") (pin "22") (pinfunction "ADC7_22") (pintype "input"))
    )
    (net (code "67") (name "unconnected-(U1-AREF-Pad20)") (class "Default")
      (node (ref "U1") (pin "20") (pinfunction "AREF_20") (pintype "power_in"))
    )
    (net (code "68") (name "unconnected-(U1-AVCC-Pad18)") (class "Default")
      (node (ref "U1") (pin "18") (pinfunction "AVCC_18") (pintype "power_in"))
    )
    (net (code "69") (name "unconnected-(U1-PB0_(ICP1)-Pad12)") (class "Default")
      (node (ref "U1") (pin "12") (pinfunction "PB0_(ICP1)_12") (pintype "bidirectional"))
    )
    (net (code "70") (name "unconnected-(U1-PB1_(OC1A)-Pad13)") (class "Default")
      (node (ref "U1") (pin "13") (pinfunction "PB1_(OC1A)_13") (pintype "bidirectional"))
    )
    (net (code "71") (name "unconnected-(U1-PB2_(~{SS}{slash}OC1B)-Pad14)") (class "Default")
      (node (ref "U1") (pin "14") (pinfunction "PB2_(~{SS}/OC1B)_14") (pintype "bidirectional"))
    )
    (net (code "72") (name "unconnected-(U1-PC0_(ADC0)-Pad23)") (class "Default")
      (node (ref "U1") (pin "23") (pinfunction "PC0_(ADC0)_23") (pintype "bidirectional"))
    )
    (net (code "73") (name "unconnected-(U1-PC1_(ADC1)-Pad24)") (class "Default")
      (node (ref "U1") (pin "24") (pinfunction "PC1_(ADC1)_24") (pintype "bidirectional"))
    )
    (net (code "74") (name "unconnected-(U1-PC2_(ADC2)-Pad25)") (class "Default")
      (node (ref "U1") (pin "25") (pinfunction "PC2_(ADC2)_25") (pintype "bidirectional"))
    )
    (net (code "75") (name "unconnected-(U1-PC3_(ADC3)-Pad26)") (class "Default")
      (node (ref "U1") (pin "26") (pinfunction "PC3_(ADC3)_26") (pintype "bidirectional"))
    )
    (net (code "76") (name "unconnected-(U1-PD3_(INT1)-Pad1)") (class "Default")
      (node (ref "U1") (pin "1") (pinfunction "PD3_(INT1)_1") (pintype "bidirectional"))
    )
    (net (code "77") (name "unconnected-(U1-PD4_(XCK{slash}T0)-Pad2)") (class "Default")
      (node (ref "U1") (pin "2") (pinfunction "PD4_(XCK/T0)_2") (pintype "bidirectional"))
    )
    (net (code "78") (name "unconnected-(U1-PD6_(AIN0)-Pad10)") (class "Default")
      (node (ref "U1") (pin "10") (pinfunction "PD6_(AIN0)_10") (pintype "bidirectional"))
    )
    (net (code "79") (name "unconnected-(U1-PD7_(AIN1)-Pad11)") (class "Default")
      (node (ref "U1") (pin "11") (pinfunction "PD7_(AIN1)_11") (pintype "bidirectional"))
    )
    (net (code "80") (name "unconnected-(U2-ADC6-Pad19)") (class "Default")
      (node (ref "U2") (pin "19") (pinfunction "ADC6_19") (pintype "input"))
    )
    (net (code "81") (name "unconnected-(U2-ADC7-Pad22)") (class "Default")
      (node (ref "U2") (pin "22") (pinfunction "ADC7_22") (pintype "input"))
    )
    (net (code "82") (name "unconnected-(U2-AREF-Pad20)") (class "Default")
      (node (ref "U2") (pin "20") (pinfunction "AREF_20") (pintype "power_in"))
    )
    (net (code "83") (name "unconnected-(U2-AVCC-Pad18)") (class "Default")
      (node (ref "U2") (pin "18") (pinfunction "AVCC_18") (pintype "power_in"))
    )
    (net (code "84") (name "unconnected-(U2-PB0_(ICP1)-Pad12)") (class "Default")
      (node (ref "U2") (pin "12") (pinfunction "PB0_(ICP1)_12") (pintype "bidirectional"))
    )
    (net (code "85") (name "unconnected-(U2-PB1_(OC1A)-Pad13)") (class "Default")
      (node (ref "U2") (pin "13") (pinfunction "PB1_(OC1A)_13") (pintype "bidirectional"))
    )
    (net (code "86") (name "unconnected-(U2-PB2_(~{SS}{slash}OC1B)-Pad14)") (class "Default")
      (node (ref "U2") (pin "14") (pinfunction "PB2_(~{SS}/OC1B)_14") (pintype "bidirectional"))
    )
    (net (code "87") (name "unconnected-(U2-PC0_(ADC0)-Pad23)") (class "Default")
      (node (ref "U2") (pin "23") (pinfunction "PC0_(ADC0)_23") (pintype "bidirectional"))
    )
    (net (code "88") (name "unconnected-(U2-PC1_(ADC1)-Pad24)") (class "Default")
      (node (ref "U2") (pin "24") (pinfunction "PC1_(ADC1)_24") (pintype "bidirectional"))
    )
    (net (code "89") (name "unconnected-(U2-PC2_(ADC2)-Pad25)") (class "Default")
      (node (ref "U2") (pin "25") (pinfunction "PC2_(ADC2)_25") (pintype "bidirectional"))
    )
    (net (code "90") (name "unconnected-(U2-PC3_(ADC3)-Pad26)") (class "Default")
      (node (ref "U2") (pin "26") (pinfunction "PC3_(ADC3)_26") (pintype "bidirectional"))
    )
    (net (code "91") (name "unconnected-(U2-PD3_(INT1)-Pad1)") (class "Default")
      (node (ref "U2") (pin "1") (pinfunction "PD3_(INT1)_1") (pintype "bidirectional"))
    )
    (net (code "92") (name "unconnected-(U2-PD4_(XCK{slash}T0)-Pad2)") (class "Default")
      (node (ref "U2") (pin "2") (pinfunction "PD4_(XCK/T0)_2") (pintype "bidirectional"))
    )
    (net (code "93") (name "unconnected-(U2-PD6_(AIN0)-Pad10)") (class "Default")
      (node (ref "U2") (pin "10") (pinfunction "PD6_(AIN0)_10") (pintype "bidirectional"))
    )
    (net (code "94") (name "unconnected-(U2-PD7_(AIN1)-Pad11)") (class "Default")
      (node (ref "U2") (pin "11") (pinfunction "PD7_(AIN1)_11") (pintype "bidirectional"))
    )
    (net (code "95") (name "unconnected-(U3-ADC6-Pad19)") (class "Default")
      (node (ref "U3") (pin "19") (pinfunction "ADC6_19") (pintype "input"))
    )
    (net (code "96") (name "unconnected-(U3-ADC7-Pad22)") (class "Default")
      (node (ref "U3") (pin "22") (pinfunction "ADC7_22") (pintype "input"))
    )
    (net (code "97") (name "unconnected-(U3-AREF-Pad20)") (class "Default")
      (node (ref "U3") (pin "20") (pinfunction "AREF_20") (pintype "power_in"))
    )
    (net (code "98") (name "unconnected-(U3-AVCC-Pad18)") (class "Default")
      (node (ref "U3") (pin "18") (pinfunction "AVCC_18") (pintype "power_in"))
    )
    (net (code "99") (name "unconnected-(U3-PB0_(ICP1)-Pad12)") (class "Default")
      (node (ref "U3") (pin "12") (pinfunction "PB0_(ICP1)_12") (pintype "bidirectional"))
    )
    (net (code "100") (name "unconnected-(U3-PB1_(OC1A)-Pad13)") (class "Default")
      (node (ref "U3") (pin "13") (pinfunction "PB1_(OC1A)_13") (pintype "bidirectional"))
    )
    (net (code "101") (name "unconnected-(U3-PB2_(~{SS}{slash}OC1B)-Pad14)") (class "Default")
      (node (ref "U3") (pin "14") (pinfunction "PB2_(~{SS}/OC1B)_14") (pintype "bidirectional"))
    )
    (net (code "102") (name "unconnected-(U3-PC0_(ADC0)-Pad23)") (class "Default")
      (node (ref "U3") (pin "23") (pinfunction "PC0_(ADC0)_23") (pintype "bidirectional"))
    )
    (net (code "103") (name "unconnected-(U3-PC1_(ADC1)-Pad24)") (class "Default")
      (node (ref "U3") (pin "24") (pinfunction "PC1_(ADC1)_24") (pintype "bidirectional"))
    )
    (net (code "104") (name "unconnected-(U3-PC2_(ADC2)-Pad25)") (class "Default")
      (node (ref "U3") (pin "25") (pinfunction "PC2_(ADC2)_25") (pintype "bidirectional"))
    )
    (net (code "105") (name "unconnected-(U3-PC3_(ADC3)-Pad26)") (class "Default")
      (node (ref "U3") (pin "26") (pinfunction "PC3_(ADC3)_26") (pintype "bidirectional"))
    )
    (net (code "106") (name "unconnected-(U3-PD3_(INT1)-Pad1)") (class "Default")
      (node (ref "U3") (pin "1") (pinfunction "PD3_(INT1)_1") (pintype "bidirectional"))
    )
    (net (code "107") (name "unconnected-(U3-PD4_(XCK{slash}T0)-Pad2)") (class "Default")
      (node (ref "U3") (pin "2") (pinfunction "PD4_(XCK/T0)_2") (pintype "bidirectional"))
    )
    (net (code "108") (name "unconnected-(U3-PD6_(AIN0)-Pad10)") (class "Default")
      (node (ref "U3") (pin "10") (pinfunction "PD6_(AIN0)_10") (pintype "bidirectional"))
    )
    (net (code "109") (name "unconnected-(U3-PD7_(AIN1)-Pad11)") (class "Default")
      (node (ref "U3") (pin "11") (pinfunction "PD7_(AIN1)_11") (pintype "bidirectional"))
    )
    (net (code "110") (name "unconnected-(U4-ADC6-Pad19)") (class "Default")
      (node (ref "U4") (pin "19") (pinfunction "ADC6_19") (pintype "input"))
    )
    (net (code "111") (name "unconnected-(U4-ADC7-Pad22)") (class "Default")
      (node (ref "U4") (pin "22") (pinfunction "ADC7_22") (pintype "input"))
    )
    (net (code "112") (name "unconnected-(U4-AREF-Pad20)") (class "Default")
      (node (ref "U4") (pin "20") (pinfunction "AREF_20") (pintype "power_in"))
    )
    (net (code "113") (name "unconnected-(U4-AVCC-Pad18)") (class "Default")
      (node (ref "U4") (pin "18") (pinfunction "AVCC_18") (pintype "power_in"))
    )
    (net (code "114") (name "unconnected-(U4-PB0_(ICP1)-Pad12)") (class "Default")
      (node (ref "U4") (pin "12") (pinfunction "PB0_(ICP1)_12") (pintype "bidirectional"))
    )
    (net (code "115") (name "unconnected-(U4-PB1_(OC1A)-Pad13)") (class "Default")
      (node (ref "U4") (pin "13") (pinfunction "PB1_(OC1A)_13") (pintype "bidirectional"))
    )
    (net (code "116") (name "unconnected-(U4-PB2_(~{SS}{slash}OC1B)-Pad14)") (class "Default")
      (node (ref "U4") (pin "14") (pinfunction "PB2_(~{SS}/OC1B)_14") (pintype "bidirectional"))
    )
    (net (code "117") (name "unconnected-(U4-PC0_(ADC0)-Pad23)") (class "Default")
      (node (ref "U4") (pin "23") (pinfunction "PC0_(ADC0)_23") (pintype "bidirectional"))
    )
    (net (code "118") (name "unconnected-(U4-PC1_(ADC1)-Pad24)") (class "Default")
      (node (ref "U4") (pin "24") (pinfunction "PC1_(ADC1)_24") (pintype "bidirectional"))
    )
    (net (code "119") (name "unconnected-(U4-PC2_(ADC2)-Pad25)") (class "Default")
      (node (ref "U4") (pin "25") (pinfunction "PC2_(ADC2)_25") (pintype "bidirectional"))
    )
    (net (code "120") (name "unconnected-(U4-PC3_(ADC3)-Pad26)") (class "Default")
      (node (ref "U4") (pin "26") (pinfunction "PC3_(ADC3)_26") (pintype "bidirectional"))
    )
    (net (code "121") (name "unconnected-(U4-PD3_(INT1)-Pad1)") (class "Default")
      (node (ref "U4") (pin "1") (pinfunction "PD3_(INT1)_1") (pintype "bidirectional"))
    )
    (net (code "122") (name "unconnected-(U4-PD4_(XCK{slash}T0)-Pad2)") (class "Default")
      (node (ref "U4") (pin "2") (pinfunction "PD4_(XCK/T0)_2") (pintype "bidirectional"))
    )
    (net (code "123") (name "unconnected-(U4-PD6_(AIN0)-Pad10)") (class "Default")
      (node (ref "U4") (pin "10") (pinfunction "PD6_(AIN0)_10") (pintype "bidirectional"))
    )
    (net (code "124") (name "unconnected-(U4-PD7_(AIN1)-Pad11)") (class "Default")
      (node (ref "U4") (pin "11") (pinfunction "PD7_(AIN1)_11") (pintype "bidirectional"))
    )
  )
)
